# 18V_ESB.net
KiCad netlist of a schematic drawn in Altium Designer
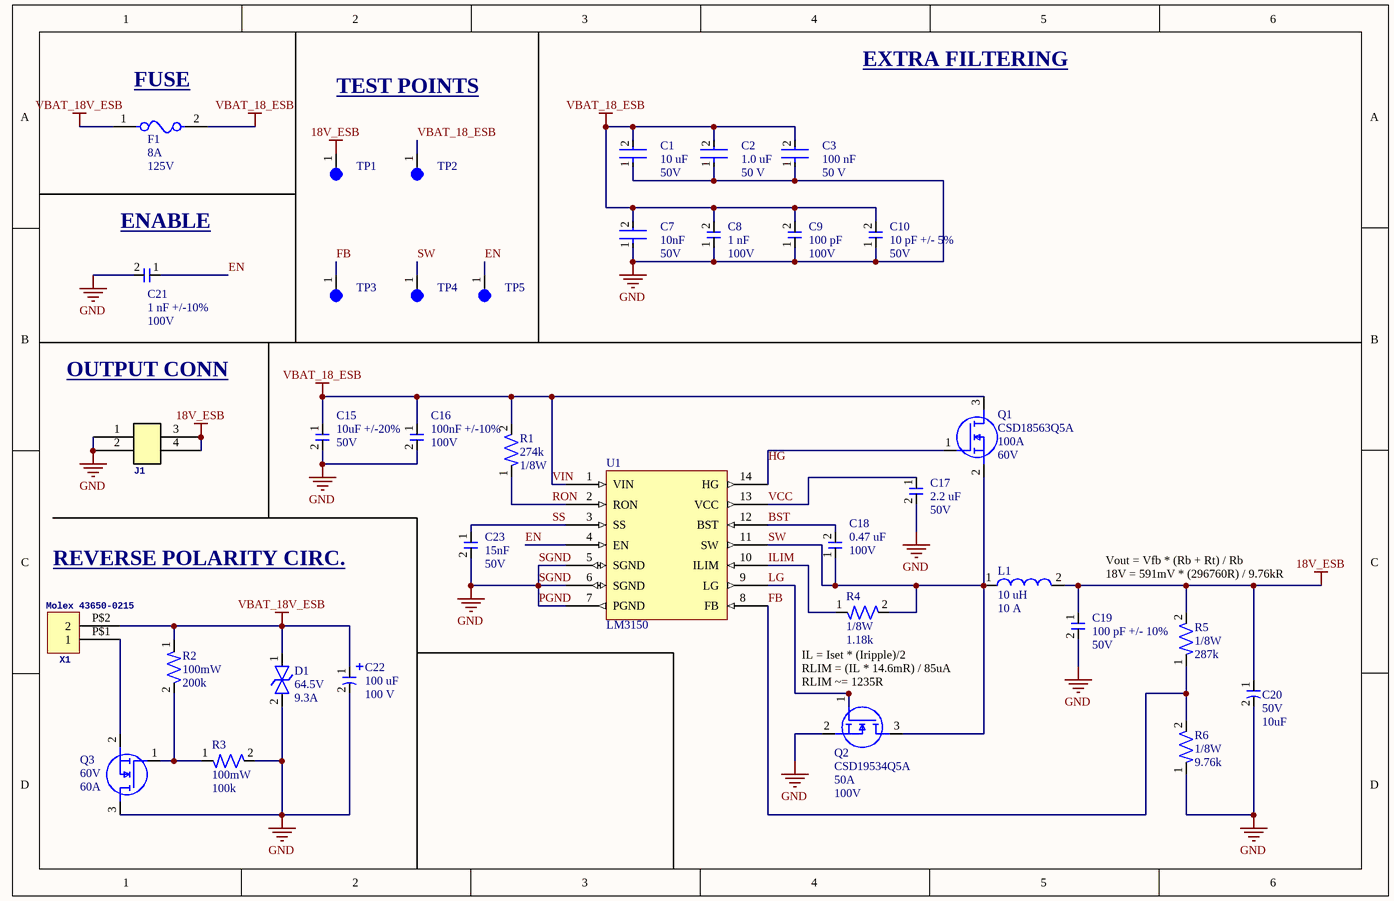
[diagram p0: 18V_ESB.SchDoc]

(export (version "E")
  (design (tool "Eeschema 10.0.6"))
  (components
    (comp (ref "C1")
      (value "CL32B106KBJNNNE")
      (footprint "MasterLib:CAP-1210")
      (description "CAP CER 10UF 50V X7R 1210")
      (fields (field (name "VOLTAGE") "50V") (field (name "CAPACITANCE") "10 uF"))
      (libsource (lib "JLC_25") (part "CAP-10U-0002"))
    )
    (comp (ref "C2")
      (value "CC0805KKX7R9BB105")
      (footprint "MasterLib:CAP-0805")
      (description "CAP CER 1UF 50V X7R 0805")
      (fields (field (name "VOLTAGE") "50 V") (field (name "CAPACITANCE") "1.0 uF"))
      (libsource (lib "JLC_25") (part "CAP-1U-0001"))
    )
    (comp (ref "C3")
      (value "CC0805KRX7R9BB104")
      (footprint "MasterLib:CAP-0805")
      (description "CAP CER 0.1UF 50V X7R 0805")
      (fields (field (name "VOLTAGE RATING") "50 V") (field (name "CAPACITANCE") "100 nF"))
      (libsource (lib "JLC_25") (part "CAP-0.1U-0002"))
    )
    (comp (ref "C7")
      (value "GRM2195C1H103JA01D")
      (footprint "MasterLib:CAP-0805")
      (description "CAP CER 10000PF 50V C0G/NP0 0805")
      (fields (field (name "VOLTAGE") "50V") (field (name "CAPACITANCE") "10nF"))
      (libsource (lib "JLC_25") (part "CAP-10N-0001"))
    )
    (comp (ref "C8")
      (value "CDR01BX102BKUS7185")
      (footprint "CAP-0805")
      (description "1000 pF ±10% 100V Ceramic Capacitor BX 0805 (2012 Metric)")
      (fields (field (name "CAPACITANCE") "1 nF") (field (name "VOLTAGE RATING") "100V"))
      (libsource (lib "MasterLib") (part "CAP-1N-0003"))
    )
    (comp (ref "C9")
      (value "0603N101J101CT")
      (footprint "CAP-0603")
      (description "100 pF ±5% 100V Ceramic Capacitor C0G, NP0 0603 (1608 Metric)")
      (fields
        (field (name "TOLERANCE") "+/-5%")
        (field (name "CAPACITANCE") "100 pF")
        (field (name "VOLTAGE") "100V")
      )
      (libsource (lib "MasterLib") (part "CAP-100P-0002"))
    )
    (comp (ref "C10")
      (value "0603N100J500CT")
      (footprint "CAP-0603")
      (description "10 pF ±5% 50V Ceramic Capacitor C0G, NP0 0603 (1608 Metric)")
      (fields
        (field (name "MANUFACTURER") "Walshin Technology Corporation")
        (field (name "CAPACITANCE") "10 pF +/- 5%")
        (field (name "VOLTAGE RATING") "50V")
      )
      (libsource (lib "MasterLib") (part "CAP-10P-0001"))
    )
    (comp (ref "C15")
      (value "CL31B106KBHNNNE")
      (footprint "CAP-1206")
      (description "10 µF ±10% 50V Ceramic Capacitor X7R 1206 (3216 Metric)")
      (fields
        (field (name "MANUFACTURER") "Samsung Electro-Mechanics")
        (field (name "CAPACITANCE") "10uF +/-20%")
        (field (name "VOLTAGE RATING") "50V")
      )
      (libsource (lib "MasterLib") (part "CAP-10U-0001"))
    )
    (comp (ref "C16")
      (value "CC0603KRX7R0BB104")
      (footprint "CAP-0603")
      (description "CAP CER 0.1UF 100V X7R 0603")
      (fields
        (field (name "MANUFACTURER") "YAGEO")
        (field (name "CAPACITANCE") "100nF +/-10%")
        (field (name "VOLTAGE RATING") "100V")
      )
      (libsource (lib "MasterLib") (part "CAP-100N-0001"))
    )
    (comp (ref "C17")
      (value "UMK107BBJ225KA-T")
      (footprint "CAP-0603")
      (description "2.2 µF ±10% 50V Ceramic Capacitor X5R 0603 (1608 Metric)")
      (fields (field (name "CAPACITANCE") "2.2 uF") (field (name "OLTAGE") "50V"))
      (libsource (lib "MasterLib") (part "CAP-2.2U-0001"))
    )
    (comp (ref "C18")
      (value "KAM21KR72A474KL")
      (footprint "CAP-0805")
      (description "0.47 µF ±10% 100V Ceramic Capacitor X7R 0805 (2012 Metric)")
      (fields
        (field (name "TOLERANCE") "+/- 10%")
        (field (name "CAPACITANCE") "0.47 uF")
        (field (name "VOLTAGE") "100V")
      )
      (libsource (lib "MasterLib") (part "CAP-0.47U-0001"))
    )
    (comp (ref "C19")
      (value "0402B101K500NT")
      (footprint "CAP-0402")
      (description "50V 100pF X7R ±10% 0402 Multilayer Ceramic Capacitors MLCC - SMD/SMT ROHS")
      (fields
        (field (name "JLC PART NUMBER") "C2991538")
        (field (name "CAPACITANCE") "100 pF +/- 10%")
        (field (name "VOLTAGE") "50V")
      )
      (libsource (lib "MasterLib") (part "CAP-100P-0001-JLC"))
    )
    (comp (ref "C20")
      (value "EEE-FK1H100UR")
      (footprint "ELEC-10uF")
      (description "10 µF 50 V Aluminum Electrolytic Capacitors Radial, Can - SMD 2000 Hrs @ 105°C")
      (fields
        (field (name "MANUFACTURER PART NUMBER") "RC0402FR-074K7P")
        (field (name "MANUFACTURER") "YAGEO")
        (field (name "VOLTAGE") "50V")
        (field (name "CAPACITANCE") "10uF")
      )
      (libsource (lib "MasterLib") (part "ELEC-10U-0001"))
    )
    (comp (ref "C21")
      (value "C0603Y102K1RAC7867")
      (footprint "CAP-0603")
      (description "1000 pF ±10% 100V Ceramic Capacitor X7R 0603 (1608 Metric)")
      (fields (field (name "CAPACITANCE") "1 nF +/-10%") (field (name "VOLTAGE") "100V"))
      (libsource (lib "MasterLib") (part "CAP-1N-0001"))
    )
    (comp (ref "C22")
      (value "100SEV100M12.5X16")
      (footprint "ELEC-100U-0001")
      (description "100 µF 100 V Aluminum Electrolytic Capacitors Radial, Can - SMD 2000 Hrs @ 85°C")
      (fields
        (field (name "MANUFACTURER") "Rubycon")
        (field (name "TOLERANCE") "+/- 20%")
        (field (name "CAPACITANCE") "100 uF")
        (field (name "VOLTAGE") "100 V")
      )
      (libsource (lib "MasterLib") (part "ELEC-100U-0001"))
    )
    (comp (ref "C23")
      (value "CC0402JRX7R9BB153")
      (footprint "CAP-0402")
      (description "CAP CER 0.015UF 50V X7R 0402")
      (fields (field (name "PARAMETER 1") "15nF") (field (name "PARAMETER 2") "50V"))
      (libsource (lib "MasterLib") (part "CAP-15N-0001"))
    )
    (comp (ref "D1")
      (value "SMBJ40CA")
      (footprint "JLC_25:DO-214AA (SMBJ)")
      (description "TVS DIODE 40VWM 64.5VC DO214AA")
      (fields (field (name "VOLTAGE RATING") "64.5V") (field (name "CURRENT RATING") "9.3A"))
      (libsource (lib "JLC_25") (part "DIO-TVS-0001"))
    )
    (comp (ref "F1")
      (value "01550900M")
      (footprint "JLC_25:FUSE-0001")
      (description "FUSE BLOK CARTRIDGE 125V 10A SMD")
      (fields (field (name "FUSE CURRENT") "8A") (field (name "VOLTAGE RATING") "125V"))
      (libsource (lib "JLC_25") (part "FUSE-0001"))
    )
    (comp (ref "J1")
      (value "Molex 43045-0412")
      (footprint "JLC_25:CONN-4POS-0002")
      (description "CONN HEADER VERT 4POS 3MM")
      (libsource (lib "JLC_25") (part "CONN-4POS-0002"))
    )
    (comp (ref "L1")
      (value "SRP1270-100M")
      (footprint "PWRIND-10U-0002")
      (description "10 µH Shielded Drum Core, Wirewound Inductor 10 A 16.8mOhm Max Nonstandard")
      (fields
        (field (name "TOLERANCE") "+/- 20%")
        (field (name "INDUCTANCE") "10 uH")
        (field (name "DCI") "10 A")
      )
      (libsource (lib "MasterLib") (part "PWRIND-10U-0002"))
    )
    (comp (ref "Q1")
      (value "CSD18563Q5A")
      (footprint "8-VSONP")
      (description "MOSFET N-CH 60V 100A 8VSON")
      (fields
        (field (name "MANUFACTURER PART NUMBER") "T2N7002AK,LM")
        (field (name "MANUFACTURER") "Toshiba")
        (field (name "ID-CONTINUOUS") "100A")
        (field (name "VDS-MAX") "60V")
      )
      (libsource (lib "MasterLib") (part "NMOS-100A-0001"))
    )
    (comp (ref "Q2")
      (value "CSD19534Q5A")
      (footprint "8-VSONP")
      (description "MOSFET N-CH 100V 50A 8VSON")
      (fields
        (field (name "MANUFACTURER PART NUMBER") "T2N7002AK,LM")
        (field (name "MANUFACTURER") "Toshiba")
        (field (name "ID-CONTINUOUS") "50A")
        (field (name "VDS-MAX") "100V")
      )
      (libsource (lib "MasterLib") (part "NMOS-50A-0001"))
    )
    (comp (ref "Q3")
      (value "CSD18543Q3AT")
      (footprint "JLC_25:IC-8VSONCLIP")
      (description "MOSFET N-CH 60V 12A/60A 8VSON")
      (fields (field (name "VOLTAGE") "60V") (field (name "CONTINUOUS CURRENT") "60A"))
      (libsource (lib "JLC_25") (part "NMOS-60A-0001"))
    )
    (comp (ref "R1")
      (value "RC0805FR-07274KL")
      (footprint "RES-0805")
      (description "274 kOhms ±1% 0.125W, 1/8W Chip Resistor 0805 (2012 Metric) Moisture Resistant Thick Film")
      (fields (field (name "RESISTANCE") "274k") (field (name "POWER") "1/8W"))
      (libsource (lib "MasterLib") (part "RES-274k-0001"))
    )
    (comp (ref "R2")
      (value "RC0603FR-07200KL")
      (footprint "MasterLib:RES-0603")
      (description "RES SMD 200K OHM 1% 1/10W 0603")
      (fields
        (field (name "TOLERANCE") "1%")
        (field (name "POWER") "100mW")
        (field (name "RESISTANCE") "200k")
      )
      (libsource (lib "JLC_25") (part "RES-200k-0001"))
    )
    (comp (ref "R3")
      (value "RC0603FR-07100KL")
      (footprint "MasterLib:RES-0603")
      (description "RES SMD 100K OHM 1% 1/10W 0603")
      (fields
        (field (name "TOLERANCE") "1%")
        (field (name "POWER") "100mW")
        (field (name "RESISTANCE") "100k")
      )
      (libsource (lib "JLC_25") (part "RES-100k-0001"))
    )
    (comp (ref "R4")
      (value "RC0805FR-071K18L")
      (footprint "RES-0805")
      (description "1.18 kOhms ±1% 0.125W, 1/8W Chip Resistor 0805 (2012 Metric) Moisture Resistant Thick Film")
      (fields (field (name "POWER") "1/8W") (field (name "RESISTANCE") "1.18k"))
      (libsource (lib "MasterLib") (part "RES-1.18k-0001"))
    )
    (comp (ref "R5")
      (value "RC0805FR-07287KL")
      (footprint "RES-0805")
      (description "287 kOhms ±1% 0.125W, 1/8W Chip Resistor 0805 (2012 Metric) Moisture Resistant Thick Film")
      (fields (field (name "POWER") "1/8W") (field (name "RESISTANCE") "287k"))
      (libsource (lib "MasterLib") (part "RES-287k-0001"))
    )
    (comp (ref "R6")
      (value "RC0805FR-079K76L")
      (footprint "RES-0805")
      (description "9.76 kOhms ±1% 0.125W, 1/8W Chip Resistor 0805 (2012 Metric) Moisture Resistant Thick Film")
      (fields (field (name "POWER") "1/8W") (field (name "RESISTANCE") "9.76k"))
      (libsource (lib "MasterLib") (part "RES-9.76k-0001"))
    )
    (comp (ref "TP1")
      (value "5003")
      (footprint "TEST-POINT-0001")
      (description "Oranange PC Test Point, Miniature Phoisphor Bronze Silver Plating Through Hole Mounting Type")
      (libsource (lib "*") (part "TEST-POINT-0001"))
    )
    (comp (ref "TP2")
      (value "5003")
      (footprint "TEST-POINT-0001")
      (description "Oranange PC Test Point, Miniature Phoisphor Bronze Silver Plating Through Hole Mounting Type")
      (libsource (lib "*") (part "TEST-POINT-0001"))
    )
    (comp (ref "TP3")
      (value "5003")
      (footprint "TEST-POINT-0001")
      (description "Oranange PC Test Point, Miniature Phoisphor Bronze Silver Plating Through Hole Mounting Type")
      (libsource (lib "*") (part "TEST-POINT-0001"))
    )
    (comp (ref "TP4")
      (value "5003")
      (footprint "TEST-POINT-0001")
      (description "Oranange PC Test Point, Miniature Phoisphor Bronze Silver Plating Through Hole Mounting Type")
      (libsource (lib "*") (part "TEST-POINT-0001"))
    )
    (comp (ref "TP5")
      (value "5003")
      (footprint "TEST-POINT-0001")
      (description "Oranange PC Test Point, Miniature Phoisphor Bronze Silver Plating Through Hole Mounting Type")
      (libsource (lib "*") (part "TEST-POINT-0001"))
    )
    (comp (ref "U1")
      (value "LM3150")
      (footprint "IC-14HTSSOP")
      (description "Buck Regulator Positive Output Step-Down DC-DC Controller IC 14-HTSSOP")
      (libsource (lib "MasterLib") (part "IC-ESB-0001"))
    )
    (comp (ref "X1")
      (value "Molex 43650-0215")
      (footprint "43650-0215")
      (libsource (lib "Molex Microfit") (part "Micro-Fit Molex 2 Pin Vertical"))
    )
  )
  (nets
    (net (code "1") (name "/BST") (class "Default")
      (node (ref "C18") (pin "2") (pinfunction "2_2") (pintype "passive"))
      (node (ref "U1") (pin "12") (pinfunction "BST_12") (pintype "input"))
    )
    (net (code "2") (name "/EN") (class "Default")
      (node (ref "C21") (pin "1") (pinfunction "1_1") (pintype "passive"))
      (node (ref "TP5") (pin "1") (pinfunction "0_1") (pintype "passive"))
      (node (ref "U1") (pin "4") (pinfunction "EN_4") (pintype "input"))
    )
    (net (code "3") (name "/FB") (class "Default")
      (node (ref "R5") (pin "1") (pinfunction "1_1") (pintype "passive"))
      (node (ref "R6") (pin "2") (pinfunction "2_2") (pintype "passive"))
      (node (ref "TP3") (pin "1") (pinfunction "0_1") (pintype "passive"))
      (node (ref "U1") (pin "8") (pinfunction "FB_8") (pintype "input"))
    )
    (net (code "4") (name "/HG") (class "Default")
      (node (ref "Q1") (pin "1") (pinfunction "G_1") (pintype "passive"))
      (node (ref "U1") (pin "14") (pinfunction "HG_14") (pintype "output"))
    )
    (net (code "5") (name "/ILIM") (class "Default")
      (node (ref "R4") (pin "1") (pinfunction "1_1") (pintype "passive"))
      (node (ref "U1") (pin "10") (pinfunction "ILIM_10") (pintype "input"))
    )
    (net (code "6") (name "/LG") (class "Default")
      (node (ref "Q2") (pin "1") (pinfunction "G_1") (pintype "passive"))
      (node (ref "U1") (pin "9") (pinfunction "LG_9") (pintype "output"))
    )
    (net (code "7") (name "/RON") (class "Default")
      (node (ref "R1") (pin "1") (pinfunction "1_1") (pintype "passive"))
      (node (ref "U1") (pin "2") (pinfunction "RON_2") (pintype "input"))
    )
    (net (code "8") (name "/SS") (class "Default")
      (node (ref "C23") (pin "1") (pinfunction "1_1") (pintype "passive"))
      (node (ref "U1") (pin "3") (pinfunction "SS_3") (pintype "input"))
    )
    (net (code "9") (name "/SW") (class "Default")
      (node (ref "C18") (pin "1") (pinfunction "1_1") (pintype "passive"))
      (node (ref "L1") (pin "1") (pinfunction "1_1") (pintype "passive"))
      (node (ref "Q1") (pin "2") (pinfunction "S_2") (pintype "passive"))
      (node (ref "Q2") (pin "3") (pinfunction "D_3") (pintype "passive"))
      (node (ref "R4") (pin "2") (pinfunction "2_2") (pintype "passive"))
      (node (ref "TP4") (pin "1") (pinfunction "0_1") (pintype "passive"))
      (node (ref "U1") (pin "11") (pinfunction "SW_11") (pintype "output"))
    )
    (net (code "10") (name "/VCC") (class "Default")
      (node (ref "C17") (pin "1") (pinfunction "1_1") (pintype "passive"))
      (node (ref "U1") (pin "13") (pinfunction "VCC_13") (pintype "output"))
    )
    (net (code "11") (name "18V_ESB") (class "Default")
      (node (ref "C19") (pin "1") (pinfunction "1_1") (pintype "passive"))
      (node (ref "C20") (pin "1") (pinfunction "1_1") (pintype "passive"))
      (node (ref "J1") (pin "3") (pinfunction "3_3") (pintype "passive"))
      (node (ref "J1") (pin "4") (pinfunction "4_4") (pintype "passive"))
      (node (ref "L1") (pin "2") (pinfunction "2_2") (pintype "passive"))
      (node (ref "R5") (pin "2") (pinfunction "2_2") (pintype "passive"))
      (node (ref "TP1") (pin "1") (pinfunction "0_1") (pintype "passive"))
    )
    (net (code "12") (name "GND") (class "Default")
      (node (ref "C1") (pin "1") (pinfunction "1_1") (pintype "passive"))
      (node (ref "C10") (pin "1") (pinfunction "1_1") (pintype "passive"))
      (node (ref "C15") (pin "2") (pinfunction "2_2") (pintype "passive"))
      (node (ref "C16") (pin "2") (pinfunction "2_2") (pintype "passive"))
      (node (ref "C17") (pin "2") (pinfunction "2_2") (pintype "passive"))
      (node (ref "C19") (pin "2") (pinfunction "2_2") (pintype "passive"))
      (node (ref "C2") (pin "1") (pinfunction "1_1") (pintype "passive"))
      (node (ref "C20") (pin "2") (pinfunction "2_2") (pintype "passive"))
      (node (ref "C21") (pin "2") (pinfunction "2_2") (pintype "passive"))
      (node (ref "C22") (pin "2") (pinfunction "2_2") (pintype "passive"))
      (node (ref "C23") (pin "2") (pinfunction "2_2") (pintype "passive"))
      (node (ref "C3") (pin "1") (pinfunction "1_1") (pintype "passive"))
      (node (ref "C7") (pin "1") (pinfunction "1_1") (pintype "passive"))
      (node (ref "C8") (pin "1") (pinfunction "1_1") (pintype "passive"))
      (node (ref "C9") (pin "1") (pinfunction "1_1") (pintype "passive"))
      (node (ref "D1") (pin "2") (pintype "passive"))
      (node (ref "J1") (pin "1") (pinfunction "1_1") (pintype "passive"))
      (node (ref "J1") (pin "2") (pinfunction "2_2") (pintype "passive"))
      (node (ref "Q2") (pin "2") (pinfunction "S_2") (pintype "passive"))
      (node (ref "Q3") (pin "3") (pinfunction "D_3") (pintype "passive"))
      (node (ref "R3") (pin "2") (pinfunction "2_2") (pintype "passive"))
      (node (ref "R6") (pin "1") (pinfunction "1_1") (pintype "passive"))
      (node (ref "U1") (pin "5") (pinfunction "SGND_5") (pintype "bidirectional"))
      (node (ref "U1") (pin "6") (pinfunction "SGND_6") (pintype "bidirectional"))
      (node (ref "U1") (pin "7") (pinfunction "PGND_7") (pintype "output"))
    )
    (net (code "13") (name "Net-(Q3-G)") (class "Default")
      (node (ref "Q3") (pin "1") (pinfunction "G_1") (pintype "passive"))
      (node (ref "R2") (pin "2") (pinfunction "2_2") (pintype "passive"))
      (node (ref "R3") (pin "1") (pinfunction "1_1") (pintype "passive"))
    )
    (net (code "14") (name "Net-(Q3-S)") (class "Default")
      (node (ref "Q3") (pin "2") (pinfunction "S_2") (pintype "passive"))
      (node (ref "X1") (pin "P$1") (pinfunction "1_P$1") (pintype "passive"))
    )
    (net (code "15") (name "VBAT_18V_ESB") (class "Default")
      (node (ref "C22") (pin "1") (pinfunction "1_1") (pintype "passive"))
      (node (ref "D1") (pin "1") (pintype "passive"))
      (node (ref "F1") (pin "1") (pinfunction "1_1") (pintype "passive"))
      (node (ref "R2") (pin "1") (pinfunction "1_1") (pintype "passive"))
      (node (ref "X1") (pin "P$2") (pinfunction "2_P$2") (pintype "passive"))
    )
    (net (code "16") (name "VBAT_18_ESB") (class "Default")
      (node (ref "C1") (pin "2") (pinfunction "2_2") (pintype "passive"))
      (node (ref "C10") (pin "2") (pinfunction "2_2") (pintype "passive"))
      (node (ref "C15") (pin "1") (pinfunction "1_1") (pintype "passive"))
      (node (ref "C16") (pin "1") (pinfunction "1_1") (pintype "passive"))
      (node (ref "C2") (pin "2") (pinfunction "2_2") (pintype "passive"))
      (node (ref "C3") (pin "2") (pinfunction "2_2") (pintype "passive"))
      (node (ref "C7") (pin "2") (pinfunction "2_2") (pintype "passive"))
      (node (ref "C8") (pin "2") (pinfunction "2_2") (pintype "passive"))
      (node (ref "C9") (pin "2") (pinfunction "2_2") (pintype "passive"))
      (node (ref "F1") (pin "2") (pinfunction "2_2") (pintype "passive"))
      (node (ref "Q1") (pin "3") (pinfunction "D_3") (pintype "passive"))
      (node (ref "R1") (pin "2") (pinfunction "2_2") (pintype "passive"))
      (node (ref "TP2") (pin "1") (pinfunction "0_1") (pintype "passive"))
      (node (ref "U1") (pin "1") (pinfunction "VIN_1") (pintype "input"))
    )
  )
)
